# Connector_circuit.net
KiCad netlist of a schematic drawn in Altium Designer
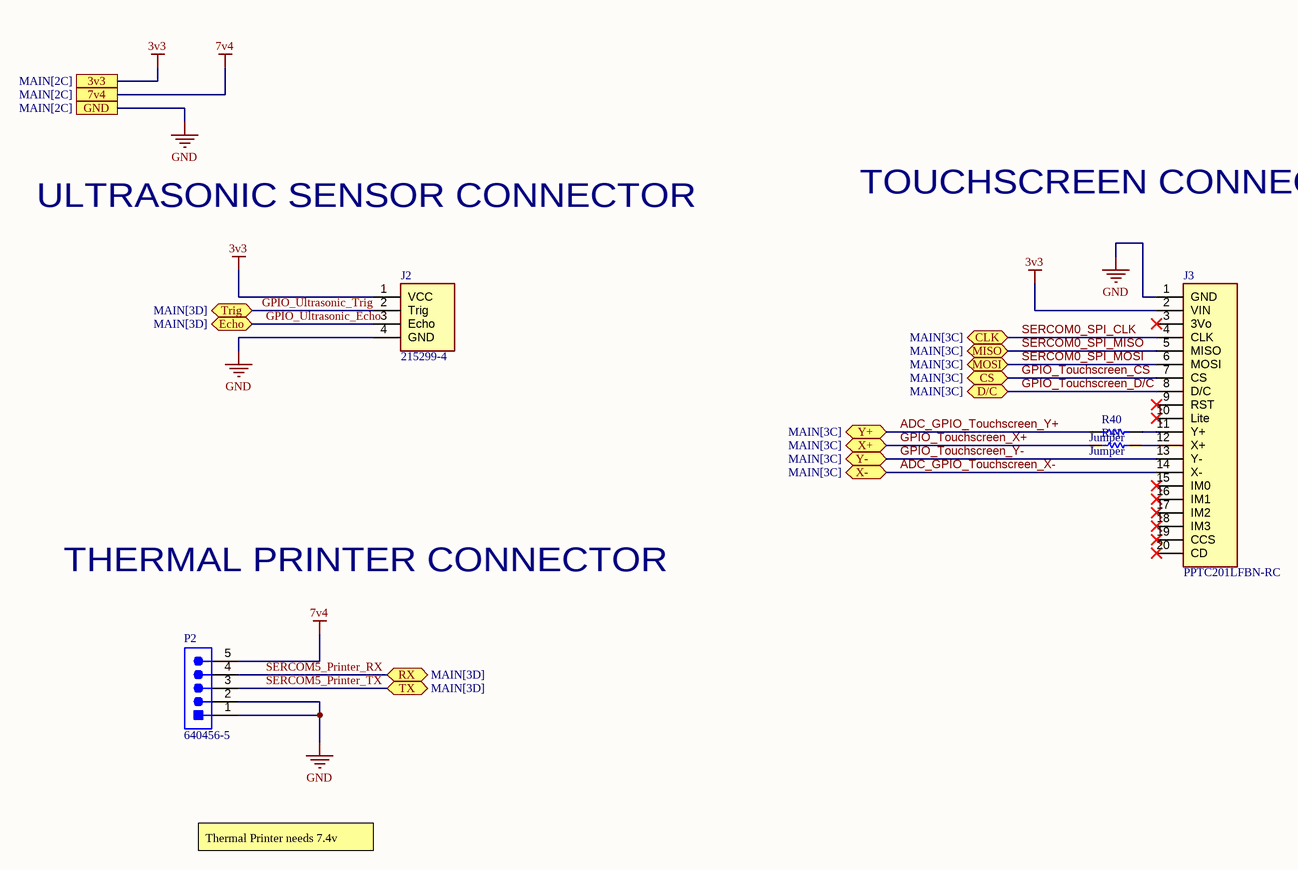
[diagram p0: Connector_circuit.SchDoc]

(export (version "E")
  (design (tool "Eeschema 10.0.6"))
  (components
    (comp (ref "J2")
      (value "215299-4")
      (footprint "TE_215299-4")
      (description "Connector")
      (libsource (lib "Schematics") (part "215299-4"))
    )
    (comp (ref "J3")
      (value "PPTC201LFBN-RC")
      (footprint "RHDR20W75P0X254_1X20_5130X254X850P")
      (description "Connector")
      (libsource (lib "Schematics") (part "PPTC201LFBN-RC"))
    )
    (comp (ref "P2")
      (value "640456-5")
      (footprint "TECO-640456-5")
      (fields (field (name "MANUFACTURER") "TE Connectivity"))
      (libsource (lib "Altium Content Vault") (part "CN-1P-M-R5"))
    )
    (comp (ref "R40")
      (value "Jumper")
      (footprint "RESC1609X50X30LL10T20")
      (fields (field (name "MANUFACTURER") "Vishay Dale") (field (name "PART NUMBER") "CRCW06030000Z0EC"))
      (libsource (lib "Altium Content Vault") (part "RES"))
    )
    (comp (ref "R41")
      (value "Jumper")
      (footprint "RESC1609X50X30LL10T20")
      (fields (field (name "MANUFACTURER") "Vishay Dale") (field (name "PART NUMBER") "CRCW06030000Z0EC"))
      (libsource (lib "Altium Content Vault") (part "RES"))
    )
  )
  (nets
    (net (code "1") (name "/ADC_GPIO_Touchscreen_X-") (class "Default")
      (node (ref "J3") (pin "14") (pinfunction "X-_14") (pintype "passive"))
    )
    (net (code "2") (name "/ADC_GPIO_Touchscreen_Y+") (class "Default")
      (node (ref "R40") (pin "1") (pinfunction "1_1") (pintype "passive"))
    )
    (net (code "3") (name "/GPIO_Touchscreen_CS") (class "Default")
      (node (ref "J3") (pin "7") (pinfunction "CS_7") (pintype "passive"))
    )
    (net (code "4") (name "/GPIO_Touchscreen_D{slash}C") (class "Default")
      (node (ref "J3") (pin "8") (pinfunction "D/C_8") (pintype "passive"))
    )
    (net (code "5") (name "/GPIO_Touchscreen_X+") (class "Default")
      (node (ref "R41") (pin "1") (pinfunction "1_1") (pintype "passive"))
    )
    (net (code "6") (name "/GPIO_Touchscreen_Y-") (class "Default")
      (node (ref "J3") (pin "13") (pinfunction "Y-_13") (pintype "passive"))
    )
    (net (code "7") (name "/GPIO_Ultrasonic_Echo") (class "Default")
      (node (ref "J2") (pin "3") (pinfunction "Echo_3") (pintype "passive"))
    )
    (net (code "8") (name "/GPIO_Ultrasonic_Trig") (class "Default")
      (node (ref "J2") (pin "2") (pinfunction "Trig_2") (pintype "passive"))
    )
    (net (code "9") (name "/SERCOM0_SPI_CLK") (class "Default")
      (node (ref "J3") (pin "4") (pinfunction "CLK_4") (pintype "passive"))
    )
    (net (code "10") (name "/SERCOM0_SPI_MISO") (class "Default")
      (node (ref "J3") (pin "5") (pinfunction "MISO_5") (pintype "passive"))
    )
    (net (code "11") (name "/SERCOM0_SPI_MOSI") (class "Default")
      (node (ref "J3") (pin "6") (pinfunction "MOSI_6") (pintype "passive"))
    )
    (net (code "12") (name "/SERCOM5_Printer_RX") (class "Default")
      (node (ref "P2") (pin "4") (pinfunction "VCC_4") (pintype "passive"))
    )
    (net (code "13") (name "/SERCOM5_Printer_TX") (class "Default")
      (node (ref "P2") (pin "3") (pinfunction "TXO_3") (pintype "passive"))
    )
    (net (code "14") (name "3v3") (class "Default")
      (node (ref "J2") (pin "1") (pinfunction "VCC_1") (pintype "passive"))
      (node (ref "J3") (pin "2") (pinfunction "VIN_2") (pintype "passive"))
    )
    (net (code "15") (name "7v4") (class "Default")
      (node (ref "P2") (pin "5") (pinfunction "CTS_5") (pintype "passive"))
    )
    (net (code "16") (name "GND") (class "Default")
      (node (ref "J2") (pin "4") (pinfunction "GND_4") (pintype "passive"))
      (node (ref "J3") (pin "1") (pinfunction "GND_1") (pintype "passive"))
      (node (ref "P2") (pin "1") (pinfunction "DTR_1") (pintype "passive"))
      (node (ref "P2") (pin "2") (pinfunction "RXI_2") (pintype "passive"))
    )
    (net (code "17") (name "Net-(J3-X+)") (class "Default")
      (node (ref "J3") (pin "12") (pinfunction "X+_12") (pintype "passive"))
      (node (ref "R41") (pin "2") (pinfunction "2_2") (pintype "passive"))
    )
    (net (code "18") (name "Net-(J3-Y+)") (class "Default")
      (node (ref "J3") (pin "11") (pinfunction "Y+_11") (pintype "passive"))
      (node (ref "R40") (pin "2") (pinfunction "2_2") (pintype "passive"))
    )
    (net (code "19") (name "unconnected-(J3-3Vo-Pad3)") (class "Default")
      (node (ref "J3") (pin "3") (pinfunction "3Vo_3") (pintype "passive+no_connect"))
    )
    (net (code "20") (name "unconnected-(J3-CCS-Pad19)") (class "Default")
      (node (ref "J3") (pin "19") (pinfunction "CCS_19") (pintype "passive+no_connect"))
    )
    (net (code "21") (name "unconnected-(J3-CD-Pad20)") (class "Default")
      (node (ref "J3") (pin "20") (pinfunction "CD_20") (pintype "passive+no_connect"))
    )
    (net (code "22") (name "unconnected-(J3-IM0-Pad15)") (class "Default")
      (node (ref "J3") (pin "15") (pinfunction "IM0_15") (pintype "passive+no_connect"))
    )
    (net (code "23") (name "unconnected-(J3-IM1-Pad16)") (class "Default")
      (node (ref "J3") (pin "16") (pinfunction "IM1_16") (pintype "passive+no_connect"))
    )
    (net (code "24") (name "unconnected-(J3-IM2-Pad17)") (class "Default")
      (node (ref "J3") (pin "17") (pinfunction "IM2_17") (pintype "passive+no_connect"))
    )
    (net (code "25") (name "unconnected-(J3-IM3-Pad18)") (class "Default")
      (node (ref "J3") (pin "18") (pinfunction "IM3_18") (pintype "passive+no_connect"))
    )
    (net (code "26") (name "unconnected-(J3-Lite-Pad10)") (class "Default")
      (node (ref "J3") (pin "10") (pinfunction "Lite_10") (pintype "passive+no_connect"))
    )
    (net (code "27") (name "unconnected-(J3-RST-Pad9)") (class "Default")
      (node (ref "J3") (pin "9") (pinfunction "RST_9") (pintype "passive+no_connect"))
    )
  )
)
